# breakout-soic8.net
KiCad netlist of a schematic drawn in EAGLE
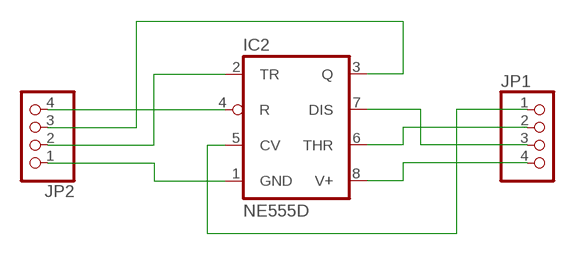
[diagram p0: schematic, sheet 1]

(export (version "E")
  (design (tool "Eeschema 10.0.6"))
  (components
    (comp (ref "IC2")
      (value "NE555D")
      (footprint "eagle-import:SO08")
      (libsource (lib "eagle-import") (part "555DNE"))
    )
    (comp (ref "JP1")
      (value "PINHD-1X4")
      (footprint "eagle-import:1X04")
      (libsource (lib "eagle-import") (part "PINHD-1X4"))
    )
    (comp (ref "JP2")
      (value "PINHD-1X4")
      (footprint "eagle-import:1X04")
      (libsource (lib "eagle-import") (part "PINHD-1X4"))
    )
  )
  (nets
    (net (code "1") (name "Net-(IC2-CV)") (class "Default")
      (node (ref "IC2") (pin "5") (pinfunction "CV_5") (pintype "input"))
      (node (ref "JP1") (pin "1") (pinfunction "1_1") (pintype "passive"))
    )
    (net (code "2") (name "Net-(IC2-DIS)") (class "Default")
      (node (ref "IC2") (pin "7") (pinfunction "DIS_7") (pintype "input"))
      (node (ref "JP1") (pin "3") (pinfunction "3_3") (pintype "passive"))
    )
    (net (code "3") (name "Net-(IC2-GND)") (class "Default")
      (node (ref "IC2") (pin "1") (pinfunction "GND_1") (pintype "power_in"))
      (node (ref "JP2") (pin "1") (pinfunction "1_1") (pintype "passive"))
    )
    (net (code "4") (name "Net-(IC2-Q)") (class "Default")
      (node (ref "IC2") (pin "3") (pinfunction "Q_3") (pintype "output"))
      (node (ref "JP2") (pin "3") (pinfunction "3_3") (pintype "passive"))
    )
    (net (code "5") (name "Net-(IC2-R)") (class "Default")
      (node (ref "IC2") (pin "4") (pinfunction "R_4") (pintype "input"))
      (node (ref "JP2") (pin "4") (pinfunction "4_4") (pintype "passive"))
    )
    (net (code "6") (name "Net-(IC2-THR)") (class "Default")
      (node (ref "IC2") (pin "6") (pinfunction "THR_6") (pintype "input"))
      (node (ref "JP1") (pin "2") (pinfunction "2_2") (pintype "passive"))
    )
    (net (code "7") (name "Net-(IC2-TR)") (class "Default")
      (node (ref "IC2") (pin "2") (pinfunction "TR_2") (pintype "input"))
      (node (ref "JP2") (pin "2") (pinfunction "2_2") (pintype "passive"))
    )
    (net (code "8") (name "Net-(IC2-V+)") (class "Default")
      (node (ref "IC2") (pin "8") (pinfunction "V+_8") (pintype "power_in"))
      (node (ref "JP1") (pin "4") (pinfunction "4_4") (pintype "passive"))
    )
  )
)
